# mosfer-board.net
KiCad netlist of a schematic drawn in EAGLE
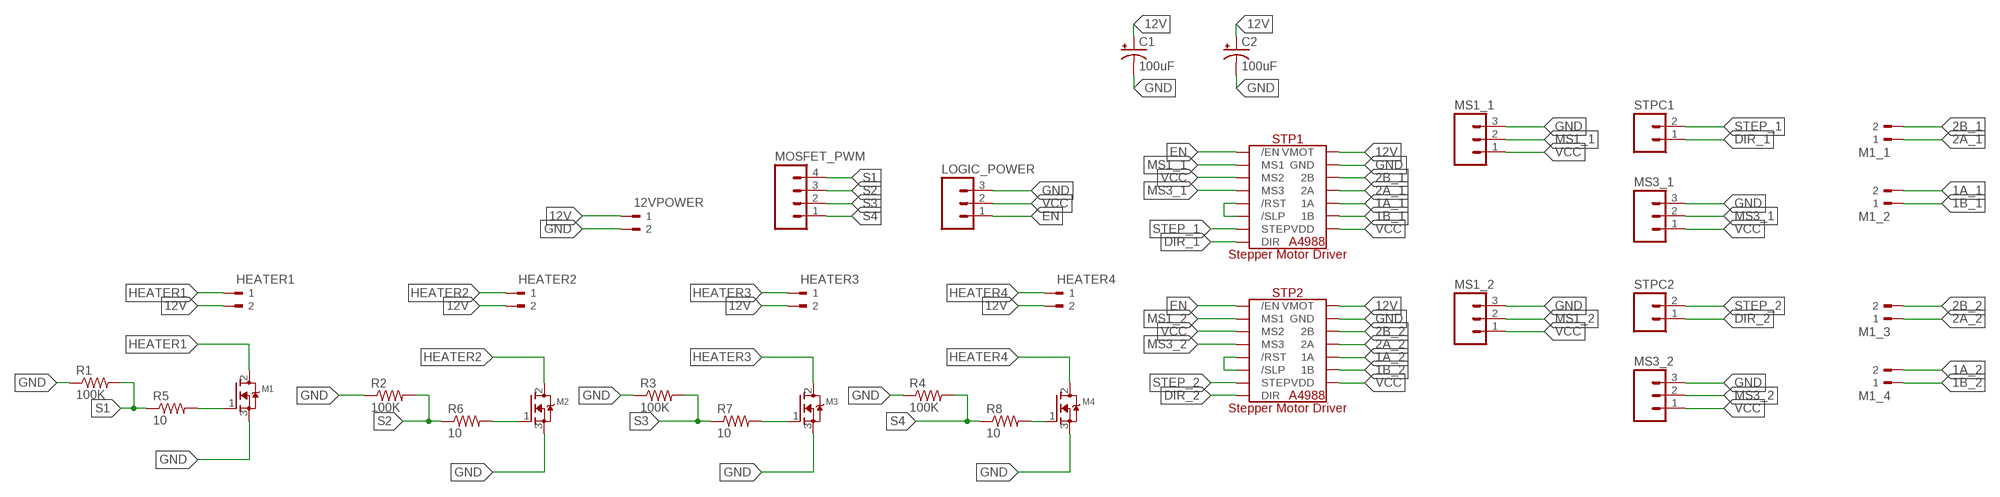
[diagram p0: schematic, sheet 1]

(export (version "E")
  (design (tool "Eeschema 10.0.6"))
  (components
    (comp (ref "12VPOWER")
      (value "PM5.08/2/90BLK")
      (footprint "eagle-import:WEIDMULLER_PM5.08_2")
      (fields (field (name "MPN") "PM5.08/2/90 BLK"))
      (libsource (lib "eagle-import") (part "PM5.08/2/90BLK"))
    )
    (comp (ref "C1")
      (value "100uF")
      (footprint "eagle-import:CPOL-RADIAL-2.5MM-6.5MM")
      (libsource (lib "eagle-import") (part "100UF-POLAR-RADIAL-2.5MM-25V-20%"))
    )
    (comp (ref "C2")
      (value "100uF")
      (footprint "eagle-import:CPOL-RADIAL-2.5MM-6.5MM")
      (libsource (lib "eagle-import") (part "100UF-POLAR-RADIAL-2.5MM-25V-20%"))
    )
    (comp (ref "HEATER1")
      (value "PM5.08/2/90BLK")
      (footprint "eagle-import:WEIDMULLER_PM5.08_2")
      (fields (field (name "MPN") "PM5.08/2/90 BLK"))
      (libsource (lib "eagle-import") (part "PM5.08/2/90BLK"))
    )
    (comp (ref "HEATER2")
      (value "PM5.08/2/90BLK")
      (footprint "eagle-import:WEIDMULLER_PM5.08_2")
      (fields (field (name "MPN") "PM5.08/2/90 BLK"))
      (libsource (lib "eagle-import") (part "PM5.08/2/90BLK"))
    )
    (comp (ref "HEATER3")
      (value "PM5.08/2/90BLK")
      (footprint "eagle-import:WEIDMULLER_PM5.08_2")
      (fields (field (name "MPN") "PM5.08/2/90 BLK"))
      (libsource (lib "eagle-import") (part "PM5.08/2/90BLK"))
    )
    (comp (ref "HEATER4")
      (value "PM5.08/2/90BLK")
      (footprint "eagle-import:WEIDMULLER_PM5.08_2")
      (fields (field (name "MPN") "PM5.08/2/90 BLK"))
      (libsource (lib "eagle-import") (part "PM5.08/2/90BLK"))
    )
    (comp (ref "LOGIC_POWER")
      (value "M03")
      (footprint "eagle-import:03P")
      (libsource (lib "eagle-import") (part "M03"))
    )
    (comp (ref "M1")
      (value "MOSFET-NGDS_TO220V")
      (footprint "eagle-import:TO220V")
      (libsource (lib "eagle-import") (part "MOSFET-NGDS_TO220V"))
    )
    (comp (ref "M1_1")
      (value "PM5.08/2/90BLK")
      (footprint "eagle-import:WEIDMULLER_PM5.08_2")
      (fields (field (name "MPN") "PM5.08/2/90 BLK"))
      (libsource (lib "eagle-import") (part "PM5.08/2/90BLK"))
    )
    (comp (ref "M1_2")
      (value "PM5.08/2/90BLK")
      (footprint "eagle-import:WEIDMULLER_PM5.08_2")
      (fields (field (name "MPN") "PM5.08/2/90 BLK"))
      (libsource (lib "eagle-import") (part "PM5.08/2/90BLK"))
    )
    (comp (ref "M1_3")
      (value "PM5.08/2/90BLK")
      (footprint "eagle-import:WEIDMULLER_PM5.08_2")
      (fields (field (name "MPN") "PM5.08/2/90 BLK"))
      (libsource (lib "eagle-import") (part "PM5.08/2/90BLK"))
    )
    (comp (ref "M1_4")
      (value "PM5.08/2/90BLK")
      (footprint "eagle-import:WEIDMULLER_PM5.08_2")
      (fields (field (name "MPN") "PM5.08/2/90 BLK"))
      (libsource (lib "eagle-import") (part "PM5.08/2/90BLK"))
    )
    (comp (ref "M2")
      (value "MOSFET-NGDS_TO220V")
      (footprint "eagle-import:TO220V")
      (libsource (lib "eagle-import") (part "MOSFET-NGDS_TO220V"))
    )
    (comp (ref "M3")
      (value "MOSFET-NGDS_TO220V")
      (footprint "eagle-import:TO220V")
      (libsource (lib "eagle-import") (part "MOSFET-NGDS_TO220V"))
    )
    (comp (ref "M4")
      (value "MOSFET-NGDS_TO220V")
      (footprint "eagle-import:TO220V")
      (libsource (lib "eagle-import") (part "MOSFET-NGDS_TO220V"))
    )
    (comp (ref "MOSFET_PWM")
      (value "M04")
      (footprint "eagle-import:04P")
      (libsource (lib "eagle-import") (part "M04"))
    )
    (comp (ref "MS1_1")
      (value "M03")
      (footprint "eagle-import:03P")
      (libsource (lib "eagle-import") (part "M03"))
    )
    (comp (ref "MS1_2")
      (value "M03")
      (footprint "eagle-import:03P")
      (libsource (lib "eagle-import") (part "M03"))
    )
    (comp (ref "MS3_1")
      (value "M03")
      (footprint "eagle-import:03P")
      (libsource (lib "eagle-import") (part "M03"))
    )
    (comp (ref "MS3_2")
      (value "M03")
      (footprint "eagle-import:03P")
      (libsource (lib "eagle-import") (part "M03"))
    )
    (comp (ref "R1")
      (value "100K")
      (footprint "eagle-import:R1206FAB")
      (libsource (lib "eagle-import") (part "RES-US1206FAB"))
    )
    (comp (ref "R2")
      (value "100K")
      (footprint "eagle-import:R1206FAB")
      (libsource (lib "eagle-import") (part "RES-US1206FAB"))
    )
    (comp (ref "R3")
      (value "100K")
      (footprint "eagle-import:R1206FAB")
      (libsource (lib "eagle-import") (part "RES-US1206FAB"))
    )
    (comp (ref "R4")
      (value "100K")
      (footprint "eagle-import:R1206FAB")
      (libsource (lib "eagle-import") (part "RES-US1206FAB"))
    )
    (comp (ref "R5")
      (value "10")
      (footprint "eagle-import:R1206FAB")
      (libsource (lib "eagle-import") (part "RES-US1206FAB"))
    )
    (comp (ref "R6")
      (value "10")
      (footprint "eagle-import:R1206FAB")
      (libsource (lib "eagle-import") (part "RES-US1206FAB"))
    )
    (comp (ref "R7")
      (value "10")
      (footprint "eagle-import:R1206FAB")
      (libsource (lib "eagle-import") (part "RES-US1206FAB"))
    )
    (comp (ref "R8")
      (value "10")
      (footprint "eagle-import:R1206FAB")
      (libsource (lib "eagle-import") (part "RES-US1206FAB"))
    )
    (comp (ref "STP1")
      (value "A4988_STEP")
      (footprint "eagle-import:A4988_STEP")
      (libsource (lib "eagle-import") (part "A4988_STEP"))
    )
    (comp (ref "STP2")
      (value "A4988_STEP")
      (footprint "eagle-import:A4988_STEP")
      (libsource (lib "eagle-import") (part "A4988_STEP"))
    )
    (comp (ref "STPC1")
      (value "M02")
      (footprint "eagle-import:02P")
      (libsource (lib "eagle-import") (part "M02"))
    )
    (comp (ref "STPC2")
      (value "M02")
      (footprint "eagle-import:02P")
      (libsource (lib "eagle-import") (part "M02"))
    )
  )
  (nets
    (net (code "1") (name "1A_1") (class "Default")
      (node (ref "M1_2") (pin "2") (pinfunction "2_2") (pintype "passive"))
      (node (ref "STP1") (pin "1A") (pinfunction "1A_1A") (pintype "bidirectional"))
    )
    (net (code "2") (name "1A_2") (class "Default")
      (node (ref "M1_4") (pin "2") (pinfunction "2_2") (pintype "passive"))
      (node (ref "STP2") (pin "1A") (pinfunction "1A_1A") (pintype "bidirectional"))
    )
    (net (code "3") (name "1B_1") (class "Default")
      (node (ref "M1_2") (pin "1") (pinfunction "1_1") (pintype "passive"))
      (node (ref "STP1") (pin "1B") (pinfunction "1B_1B") (pintype "bidirectional"))
    )
    (net (code "4") (name "1B_2") (class "Default")
      (node (ref "M1_4") (pin "1") (pinfunction "1_1") (pintype "passive"))
      (node (ref "STP2") (pin "1B") (pinfunction "1B_1B") (pintype "bidirectional"))
    )
    (net (code "5") (name "2A_1") (class "Default")
      (node (ref "M1_1") (pin "1") (pinfunction "1_1") (pintype "passive"))
      (node (ref "STP1") (pin "2A") (pinfunction "2A_2A") (pintype "bidirectional"))
    )
    (net (code "6") (name "2A_2") (class "Default")
      (node (ref "M1_3") (pin "1") (pinfunction "1_1") (pintype "passive"))
      (node (ref "STP2") (pin "2A") (pinfunction "2A_2A") (pintype "bidirectional"))
    )
    (net (code "7") (name "2B_1") (class "Default")
      (node (ref "M1_1") (pin "2") (pinfunction "2_2") (pintype "passive"))
      (node (ref "STP1") (pin "2B") (pinfunction "2B_2B") (pintype "bidirectional"))
    )
    (net (code "8") (name "2B_2") (class "Default")
      (node (ref "M1_3") (pin "2") (pinfunction "2_2") (pintype "passive"))
      (node (ref "STP2") (pin "2B") (pinfunction "2B_2B") (pintype "bidirectional"))
    )
    (net (code "9") (name "12V") (class "Default")
      (node (ref "12VPOWER") (pin "1") (pinfunction "1_1") (pintype "passive"))
      (node (ref "C1") (pin "1") (pinfunction "+_1") (pintype "passive"))
      (node (ref "C2") (pin "1") (pinfunction "+_1") (pintype "passive"))
      (node (ref "HEATER1") (pin "2") (pinfunction "2_2") (pintype "passive"))
      (node (ref "HEATER2") (pin "2") (pinfunction "2_2") (pintype "passive"))
      (node (ref "HEATER3") (pin "2") (pinfunction "2_2") (pintype "passive"))
      (node (ref "HEATER4") (pin "2") (pinfunction "2_2") (pintype "passive"))
      (node (ref "STP1") (pin "VMOT") (pinfunction "VMOT_VMOT") (pintype "bidirectional"))
      (node (ref "STP2") (pin "VMOT") (pinfunction "VMOT_VMOT") (pintype "bidirectional"))
    )
    (net (code "10") (name "DIR_1") (class "Default")
      (node (ref "STP1") (pin "DIR") (pinfunction "DIR_DIR") (pintype "bidirectional"))
      (node (ref "STPC1") (pin "1") (pinfunction "1_1") (pintype "passive"))
    )
    (net (code "11") (name "DIR_2") (class "Default")
      (node (ref "STP2") (pin "DIR") (pinfunction "DIR_DIR") (pintype "bidirectional"))
      (node (ref "STPC2") (pin "1") (pinfunction "1_1") (pintype "passive"))
    )
    (net (code "12") (name "EN") (class "Default")
      (node (ref "LOGIC_POWER") (pin "1") (pinfunction "1_1") (pintype "passive"))
      (node (ref "STP1") (pin "/EN") (pinfunction "/EN_/EN") (pintype "bidirectional"))
      (node (ref "STP2") (pin "/EN") (pinfunction "/EN_/EN") (pintype "bidirectional"))
    )
    (net (code "13") (name "GND") (class "Default")
      (node (ref "12VPOWER") (pin "2") (pinfunction "2_2") (pintype "passive"))
      (node (ref "C1") (pin "2") (pinfunction "-_2") (pintype "passive"))
      (node (ref "C2") (pin "2") (pinfunction "-_2") (pintype "passive"))
      (node (ref "LOGIC_POWER") (pin "3") (pinfunction "3_3") (pintype "passive"))
      (node (ref "M1") (pin "3") (pinfunction "S_3") (pintype "bidirectional"))
      (node (ref "M2") (pin "3") (pinfunction "S_3") (pintype "bidirectional"))
      (node (ref "M3") (pin "3") (pinfunction "S_3") (pintype "bidirectional"))
      (node (ref "M4") (pin "3") (pinfunction "S_3") (pintype "bidirectional"))
      (node (ref "MS1_1") (pin "3") (pinfunction "3_3") (pintype "passive"))
      (node (ref "MS1_2") (pin "3") (pinfunction "3_3") (pintype "passive"))
      (node (ref "MS3_1") (pin "3") (pinfunction "3_3") (pintype "passive"))
      (node (ref "MS3_2") (pin "3") (pinfunction "3_3") (pintype "passive"))
      (node (ref "R1") (pin "1") (pinfunction "1_1") (pintype "passive"))
      (node (ref "R2") (pin "1") (pinfunction "1_1") (pintype "passive"))
      (node (ref "R3") (pin "1") (pinfunction "1_1") (pintype "passive"))
      (node (ref "R4") (pin "1") (pinfunction "1_1") (pintype "passive"))
      (node (ref "STP1") (pin "GND") (pinfunction "GND_GND") (pintype "bidirectional"))
      (node (ref "STP1") (pin "GND2") (pinfunction "GND_GND2") (pintype "bidirectional"))
      (node (ref "STP2") (pin "GND") (pinfunction "GND_GND") (pintype "bidirectional"))
      (node (ref "STP2") (pin "GND2") (pinfunction "GND_GND2") (pintype "bidirectional"))
    )
    (net (code "14") (name "HEATER1") (class "Default")
      (node (ref "HEATER1") (pin "1") (pinfunction "1_1") (pintype "passive"))
      (node (ref "M1") (pin "2") (pinfunction "D_2") (pintype "bidirectional"))
    )
    (net (code "15") (name "HEATER2") (class "Default")
      (node (ref "HEATER2") (pin "1") (pinfunction "1_1") (pintype "passive"))
      (node (ref "M2") (pin "2") (pinfunction "D_2") (pintype "bidirectional"))
    )
    (net (code "16") (name "HEATER3") (class "Default")
      (node (ref "HEATER3") (pin "1") (pinfunction "1_1") (pintype "passive"))
      (node (ref "M3") (pin "2") (pinfunction "D_2") (pintype "bidirectional"))
    )
    (net (code "17") (name "HEATER4") (class "Default")
      (node (ref "HEATER4") (pin "1") (pinfunction "1_1") (pintype "passive"))
      (node (ref "M4") (pin "2") (pinfunction "D_2") (pintype "bidirectional"))
    )
    (net (code "18") (name "MS1_1") (class "Default")
      (node (ref "MS1_1") (pin "2") (pinfunction "2_2") (pintype "passive"))
      (node (ref "STP1") (pin "MS1") (pinfunction "MS1_MS1") (pintype "bidirectional"))
    )
    (net (code "19") (name "MS1_2") (class "Default")
      (node (ref "MS1_2") (pin "2") (pinfunction "2_2") (pintype "passive"))
      (node (ref "STP2") (pin "MS1") (pinfunction "MS1_MS1") (pintype "bidirectional"))
    )
    (net (code "20") (name "MS3_1") (class "Default")
      (node (ref "MS3_1") (pin "2") (pinfunction "2_2") (pintype "passive"))
      (node (ref "STP1") (pin "MS3") (pinfunction "MS3_MS3") (pintype "bidirectional"))
    )
    (net (code "21") (name "MS3_2") (class "Default")
      (node (ref "MS3_2") (pin "2") (pinfunction "2_2") (pintype "passive"))
      (node (ref "STP2") (pin "MS3") (pinfunction "MS3_MS3") (pintype "bidirectional"))
    )
    (net (code "22") (name "Net-(M1-G)") (class "Default")
      (node (ref "M1") (pin "1") (pinfunction "G_1") (pintype "bidirectional"))
      (node (ref "R5") (pin "2") (pinfunction "2_2") (pintype "passive"))
    )
    (net (code "23") (name "Net-(M2-G)") (class "Default")
      (node (ref "M2") (pin "1") (pinfunction "G_1") (pintype "bidirectional"))
      (node (ref "R6") (pin "2") (pinfunction "2_2") (pintype "passive"))
    )
    (net (code "24") (name "Net-(M3-G)") (class "Default")
      (node (ref "M3") (pin "1") (pinfunction "G_1") (pintype "bidirectional"))
      (node (ref "R7") (pin "2") (pinfunction "2_2") (pintype "passive"))
    )
    (net (code "25") (name "Net-(M4-G)") (class "Default")
      (node (ref "M4") (pin "1") (pinfunction "G_1") (pintype "bidirectional"))
      (node (ref "R8") (pin "2") (pinfunction "2_2") (pintype "passive"))
    )
    (net (code "26") (name "Net-(STP1-Pad{slash}RST)") (class "Default")
      (node (ref "STP1") (pin "/RST") (pinfunction "/RST_/RST") (pintype "bidirectional"))
      (node (ref "STP1") (pin "/SLP") (pinfunction "/SLP_/SLP") (pintype "bidirectional"))
    )
    (net (code "27") (name "Net-(STP2-Pad{slash}RST)") (class "Default")
      (node (ref "STP2") (pin "/RST") (pinfunction "/RST_/RST") (pintype "bidirectional"))
      (node (ref "STP2") (pin "/SLP") (pinfunction "/SLP_/SLP") (pintype "bidirectional"))
    )
    (net (code "28") (name "S1") (class "Default")
      (node (ref "MOSFET_PWM") (pin "4") (pinfunction "4_4") (pintype "passive"))
      (node (ref "R1") (pin "2") (pinfunction "2_2") (pintype "passive"))
      (node (ref "R5") (pin "1") (pinfunction "1_1") (pintype "passive"))
    )
    (net (code "29") (name "S2") (class "Default")
      (node (ref "MOSFET_PWM") (pin "3") (pinfunction "3_3") (pintype "passive"))
      (node (ref "R2") (pin "2") (pinfunction "2_2") (pintype "passive"))
      (node (ref "R6") (pin "1") (pinfunction "1_1") (pintype "passive"))
    )
    (net (code "30") (name "S3") (class "Default")
      (node (ref "MOSFET_PWM") (pin "2") (pinfunction "2_2") (pintype "passive"))
      (node (ref "R3") (pin "2") (pinfunction "2_2") (pintype "passive"))
      (node (ref "R7") (pin "1") (pinfunction "1_1") (pintype "passive"))
    )
    (net (code "31") (name "S4") (class "Default")
      (node (ref "MOSFET_PWM") (pin "1") (pinfunction "1_1") (pintype "passive"))
      (node (ref "R4") (pin "2") (pinfunction "2_2") (pintype "passive"))
      (node (ref "R8") (pin "1") (pinfunction "1_1") (pintype "passive"))
    )
    (net (code "32") (name "STEP_1") (class "Default")
      (node (ref "STP1") (pin "STEP") (pinfunction "STEP_STEP") (pintype "bidirectional"))
      (node (ref "STPC1") (pin "2") (pinfunction "2_2") (pintype "passive"))
    )
    (net (code "33") (name "STEP_2") (class "Default")
      (node (ref "STP2") (pin "STEP") (pinfunction "STEP_STEP") (pintype "bidirectional"))
      (node (ref "STPC2") (pin "2") (pinfunction "2_2") (pintype "passive"))
    )
    (net (code "34") (name "VCC") (class "Default")
      (node (ref "LOGIC_POWER") (pin "2") (pinfunction "2_2") (pintype "passive"))
      (node (ref "MS1_1") (pin "1") (pinfunction "1_1") (pintype "passive"))
      (node (ref "MS1_2") (pin "1") (pinfunction "1_1") (pintype "passive"))
      (node (ref "MS3_1") (pin "1") (pinfunction "1_1") (pintype "passive"))
      (node (ref "MS3_2") (pin "1") (pinfunction "1_1") (pintype "passive"))
      (node (ref "STP1") (pin "MS2") (pinfunction "MS2_MS2") (pintype "bidirectional"))
      (node (ref "STP1") (pin "VDD") (pinfunction "VDD_VDD") (pintype "bidirectional"))
      (node (ref "STP2") (pin "MS2") (pinfunction "MS2_MS2") (pintype "bidirectional"))
      (node (ref "STP2") (pin "VDD") (pinfunction "VDD_VDD") (pintype "bidirectional"))
    )
  )
)
